# InkTime.net
KiCad netlist of a schematic drawn in EAGLE
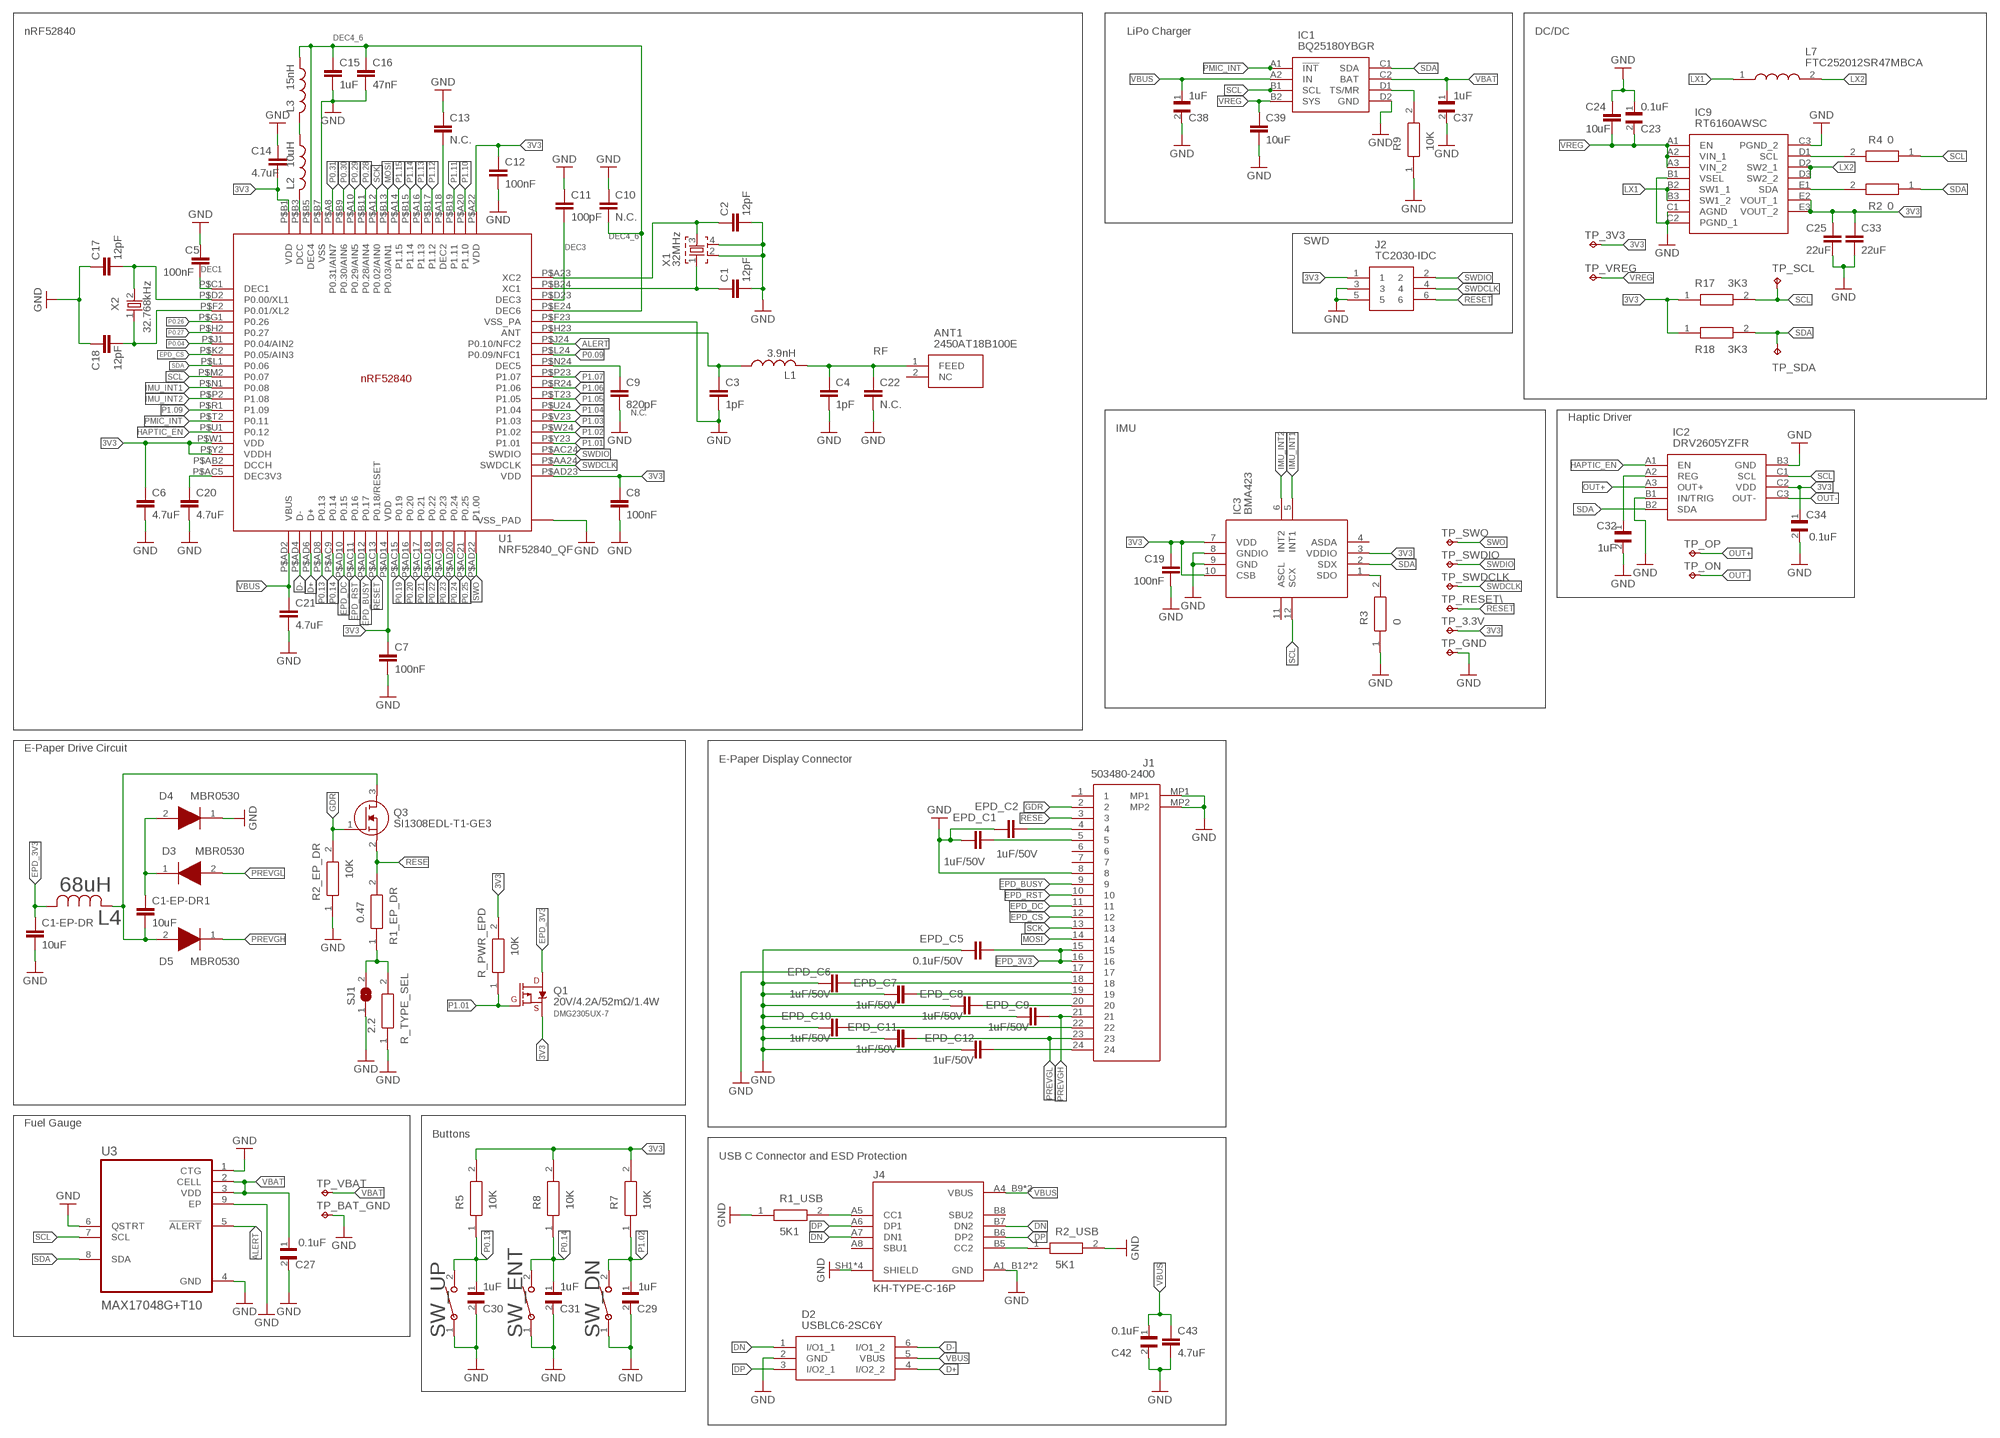
[diagram p0: schematic, sheet 1]

(export (version "E")
  (design (tool "Eeschema 10.0.6"))
  (components
    (comp (ref "ANT1")
      (value "2450AT18B100E")
      (footprint "eagle-import:2450AT18B100E_ANTC3216X140N")
      (fields (field (name "MOUSER_PART_NUMBER") "609-2450AT18B100E"))
      (libsource (lib "eagle-import") (part "2450AT18B100E_2450AT18B100E"))
    )
    (comp (ref "C1")
      (value "12pF")
      (footprint "eagle-import:NORDIC_NRF_3_RESC0201_L")
      (libsource (lib "eagle-import") (part "InkTime_v5_vf.MLmYuSJKQ5Wbrkh9WamEiQ_NORDIC_NRF_3_CAPACITOR_0201_L"))
    )
    (comp (ref "C1-EP-DR")
      (value "10uF")
      (footprint "eagle-import:NORDIC_NRF_3_RESC0402_L")
      (libsource (lib "eagle-import") (part "InkTime_v5_vf.MLmYuSJKQ5Wbrkh9WamEiQ_NORDIC_NRF_3_CAPACITOR_0402_L"))
    )
    (comp (ref "C1-EP-DR1")
      (value "10uF")
      (footprint "eagle-import:NORDIC_NRF_3_RESC0402_L")
      (libsource (lib "eagle-import") (part "InkTime_v5_vf.MLmYuSJKQ5Wbrkh9WamEiQ_NORDIC_NRF_3_CAPACITOR_0402_L"))
    )
    (comp (ref "C2")
      (value "12pF")
      (footprint "eagle-import:NORDIC_NRF_3_RESC0201_L")
      (libsource (lib "eagle-import") (part "InkTime_v5_vf.MLmYuSJKQ5Wbrkh9WamEiQ_NORDIC_NRF_3_CAPACITOR_0201_L"))
    )
    (comp (ref "C3")
      (value "1pF")
      (footprint "eagle-import:NORDIC_NRF_3_RESC0201_L")
      (libsource (lib "eagle-import") (part "InkTime_v5_vf.MLmYuSJKQ5Wbrkh9WamEiQ_NORDIC_NRF_3_CAPACITOR_0201_L"))
    )
    (comp (ref "C4")
      (value "1pF")
      (footprint "eagle-import:NORDIC_NRF_3_RESC0201_L")
      (libsource (lib "eagle-import") (part "InkTime_v5_vf.MLmYuSJKQ5Wbrkh9WamEiQ_NORDIC_NRF_3_CAPACITOR_0201_L"))
    )
    (comp (ref "C5")
      (value "100nF")
      (footprint "eagle-import:NORDIC_NRF_3_RESC0201_L")
      (libsource (lib "eagle-import") (part "InkTime_v5_vf.MLmYuSJKQ5Wbrkh9WamEiQ_NORDIC_NRF_3_CAPACITOR_0201_L"))
    )
    (comp (ref "C6")
      (value "4.7uF")
      (footprint "eagle-import:NORDIC_NRF_3_RESC0402_L")
      (libsource (lib "eagle-import") (part "InkTime_v5_vf.MLmYuSJKQ5Wbrkh9WamEiQ_NORDIC_NRF_3_CAPACITOR_0402_L"))
    )
    (comp (ref "C7")
      (value "100nF")
      (footprint "eagle-import:NORDIC_NRF_3_RESC0201_L")
      (libsource (lib "eagle-import") (part "InkTime_v5_vf.MLmYuSJKQ5Wbrkh9WamEiQ_NORDIC_NRF_3_CAPACITOR_0201_L"))
    )
    (comp (ref "C8")
      (value "100nF")
      (footprint "eagle-import:NORDIC_NRF_3_RESC0201_L")
      (libsource (lib "eagle-import") (part "InkTime_v5_vf.MLmYuSJKQ5Wbrkh9WamEiQ_NORDIC_NRF_3_CAPACITOR_0201_L"))
    )
    (comp (ref "C9")
      (value "820pF")
      (footprint "eagle-import:NORDIC_NRF_3_RESC0201_L")
      (libsource (lib "eagle-import") (part "InkTime_v5_vf.MLmYuSJKQ5Wbrkh9WamEiQ_NORDIC_NRF_3_CAPACITOR_0201_L"))
    )
    (comp (ref "C10")
      (value "N.C.")
      (footprint "eagle-import:NORDIC_NRF_3_RESC0201_L")
      (libsource (lib "eagle-import") (part "InkTime_v5_vf.MLmYuSJKQ5Wbrkh9WamEiQ_NORDIC_NRF_3_CAPACITOR_0201_L"))
    )
    (comp (ref "C11")
      (value "100pF")
      (footprint "eagle-import:NORDIC_NRF_3_RESC0201_L")
      (libsource (lib "eagle-import") (part "InkTime_v5_vf.MLmYuSJKQ5Wbrkh9WamEiQ_NORDIC_NRF_3_CAPACITOR_0201_L"))
    )
    (comp (ref "C12")
      (value "100nF")
      (footprint "eagle-import:NORDIC_NRF_3_RESC0201_L")
      (libsource (lib "eagle-import") (part "InkTime_v5_vf.MLmYuSJKQ5Wbrkh9WamEiQ_NORDIC_NRF_3_CAPACITOR_0201_L"))
    )
    (comp (ref "C13")
      (value "N.C.")
      (footprint "eagle-import:NORDIC_NRF_3_RESC0201_L")
      (libsource (lib "eagle-import") (part "InkTime_v5_vf.MLmYuSJKQ5Wbrkh9WamEiQ_NORDIC_NRF_3_CAPACITOR_0201_L"))
    )
    (comp (ref "C14")
      (value "4.7uF")
      (footprint "eagle-import:NORDIC_NRF_3_RESC0402_L")
      (libsource (lib "eagle-import") (part "InkTime_v5_vf.MLmYuSJKQ5Wbrkh9WamEiQ_NORDIC_NRF_3_CAPACITOR_0402_L"))
    )
    (comp (ref "C15")
      (value "1uF")
      (footprint "eagle-import:NORDIC_NRF_3_RESC0402_L")
      (libsource (lib "eagle-import") (part "InkTime_v5_vf.MLmYuSJKQ5Wbrkh9WamEiQ_NORDIC_NRF_3_CAPACITOR_0402_L"))
    )
    (comp (ref "C16")
      (value "47nF")
      (footprint "eagle-import:NORDIC_NRF_3_RESC0201_L")
      (libsource (lib "eagle-import") (part "InkTime_v5_vf.MLmYuSJKQ5Wbrkh9WamEiQ_NORDIC_NRF_3_CAPACITOR_0201_L"))
    )
    (comp (ref "C17")
      (value "12pF")
      (footprint "eagle-import:NORDIC_NRF_3_RESC0201_L")
      (libsource (lib "eagle-import") (part "InkTime_v5_vf.MLmYuSJKQ5Wbrkh9WamEiQ_NORDIC_NRF_3_CAPACITOR_0201_L"))
    )
    (comp (ref "C18")
      (value "12pF")
      (footprint "eagle-import:NORDIC_NRF_3_RESC0201_L")
      (libsource (lib "eagle-import") (part "InkTime_v5_vf.MLmYuSJKQ5Wbrkh9WamEiQ_NORDIC_NRF_3_CAPACITOR_0201_L"))
    )
    (comp (ref "C19")
      (value "100nF")
      (footprint "eagle-import:NORDIC_NRF_3_RESC0201_L")
      (libsource (lib "eagle-import") (part "InkTime_v5_vf.MLmYuSJKQ5Wbrkh9WamEiQ_NORDIC_NRF_3_CAPACITOR_0201_L"))
    )
    (comp (ref "C20")
      (value "4.7uF")
      (footprint "eagle-import:NORDIC_NRF_3_RESC0402_L")
      (libsource (lib "eagle-import") (part "InkTime_v5_vf.MLmYuSJKQ5Wbrkh9WamEiQ_NORDIC_NRF_3_CAPACITOR_0402_L"))
    )
    (comp (ref "C21")
      (value "4.7uF")
      (footprint "eagle-import:NORDIC_NRF_3_RESC0402_L")
      (libsource (lib "eagle-import") (part "InkTime_v5_vf.MLmYuSJKQ5Wbrkh9WamEiQ_NORDIC_NRF_3_CAPACITOR_0402_L"))
    )
    (comp (ref "C22")
      (value "N.C.")
      (footprint "eagle-import:NORDIC_NRF_3_RESC0201_L")
      (libsource (lib "eagle-import") (part "InkTime_v5_vf.MLmYuSJKQ5Wbrkh9WamEiQ_NORDIC_NRF_3_CAPACITOR_0201_L"))
    )
    (comp (ref "C23")
      (value "0.1uF")
      (footprint "eagle-import:GRM011R60J152KE01L_2_CAPC0201X13N")
      (fields (field (name "MF") "Murata") (field (name "MP") "GRM011R60J152KE01L"))
      (libsource (lib "eagle-import") (part "GRM011R60J152KE01L_2_GRM011R60J152KE01L"))
    )
    (comp (ref "C24")
      (value "10uF")
      (footprint "eagle-import:NORDIC_NRF_3_RESC0402_L")
      (libsource (lib "eagle-import") (part "InkTime_v5_vf.MLmYuSJKQ5Wbrkh9WamEiQ_NORDIC_NRF_3_CAPACITOR_0402_L"))
    )
    (comp (ref "C25")
      (value "22uF")
      (footprint "eagle-import:NORDIC_NRF_3_RESC0402_L")
      (libsource (lib "eagle-import") (part "InkTime_v5_vf.MLmYuSJKQ5Wbrkh9WamEiQ_NORDIC_NRF_3_CAPACITOR_0402_L"))
    )
    (comp (ref "C27")
      (value "0.1uF")
      (footprint "eagle-import:GRM011R60J152KE01L_2_CAPC0201X13N")
      (fields (field (name "MF") "Murata") (field (name "MP") "GRM011R60J152KE01L"))
      (libsource (lib "eagle-import") (part "GRM011R60J152KE01L_2_GRM011R60J152KE01L"))
    )
    (comp (ref "C29")
      (value "1uF")
      (footprint "eagle-import:GRM011R60J152KE01L_2_CAPC0201X13N")
      (fields (field (name "MF") "Murata") (field (name "MP") "GRM011R60J152KE01L"))
      (libsource (lib "eagle-import") (part "GRM011R60J152KE01L_2_GRM011R60J152KE01L"))
    )
    (comp (ref "C30")
      (value "1uF")
      (footprint "eagle-import:GRM011R60J152KE01L_2_CAPC0201X13N")
      (fields (field (name "MF") "Murata") (field (name "MP") "GRM011R60J152KE01L"))
      (libsource (lib "eagle-import") (part "GRM011R60J152KE01L_2_GRM011R60J152KE01L"))
    )
    (comp (ref "C31")
      (value "1uF")
      (footprint "eagle-import:GRM011R60J152KE01L_2_CAPC0201X13N")
      (fields (field (name "MF") "Murata") (field (name "MP") "GRM011R60J152KE01L"))
      (libsource (lib "eagle-import") (part "GRM011R60J152KE01L_2_GRM011R60J152KE01L"))
    )
    (comp (ref "C32")
      (value "1uF")
      (footprint "eagle-import:GRM011R60J152KE01L_2_CAPC0201X13N")
      (fields (field (name "MF") "Murata") (field (name "MP") "GRM011R60J152KE01L"))
      (libsource (lib "eagle-import") (part "GRM011R60J152KE01L_2_GRM011R60J152KE01L"))
    )
    (comp (ref "C33")
      (value "22uF")
      (footprint "eagle-import:NORDIC_NRF_3_RESC0402_L")
      (libsource (lib "eagle-import") (part "InkTime_v5_vf.MLmYuSJKQ5Wbrkh9WamEiQ_NORDIC_NRF_3_CAPACITOR_0402_L"))
    )
    (comp (ref "C34")
      (value "0.1uF")
      (footprint "eagle-import:GRM011R60J152KE01L_2_CAPC0201X13N")
      (fields (field (name "MF") "Murata") (field (name "MP") "GRM011R60J152KE01L"))
      (libsource (lib "eagle-import") (part "GRM011R60J152KE01L_2_GRM011R60J152KE01L"))
    )
    (comp (ref "C37")
      (value "1uF")
      (footprint "eagle-import:GRM011R60J152KE01L_2_CAPC0201X13N")
      (fields (field (name "MF") "Murata") (field (name "MP") "GRM011R60J152KE01L"))
      (libsource (lib "eagle-import") (part "GRM011R60J152KE01L_2_GRM011R60J152KE01L"))
    )
    (comp (ref "C38")
      (value "1uF")
      (footprint "eagle-import:GRM011R60J152KE01L_2_CAPC0201X13N")
      (fields (field (name "MF") "Murata") (field (name "MP") "GRM011R60J152KE01L"))
      (libsource (lib "eagle-import") (part "GRM011R60J152KE01L_2_GRM011R60J152KE01L"))
    )
    (comp (ref "C39")
      (value "10uF")
      (footprint "eagle-import:NORDIC_NRF_3_RESC0402_L")
      (libsource (lib "eagle-import") (part "InkTime_v5_vf.MLmYuSJKQ5Wbrkh9WamEiQ_NORDIC_NRF_3_CAPACITOR_0402_L"))
    )
    (comp (ref "C42")
      (value "0.1uF")
      (footprint "eagle-import:GRM011R60J152KE01L_2_CAPC0201X13N")
      (fields (field (name "MF") "Murata") (field (name "MP") "GRM011R60J152KE01L"))
      (libsource (lib "eagle-import") (part "GRM011R60J152KE01L_2_GRM011R60J152KE01L"))
    )
    (comp (ref "C43")
      (value "4.7uF")
      (footprint "eagle-import:NORDIC_NRF_3_RESC0402_L")
      (libsource (lib "eagle-import") (part "InkTime_v5_vf.MLmYuSJKQ5Wbrkh9WamEiQ_NORDIC_NRF_3_CAPACITOR_0402_L"))
    )
    (comp (ref "D2")
      (value "USBLC6-2SC6Y")
      (footprint "eagle-import:ESP32_C6_LIBRARY_3_SOT95P280X145-6N")
      (fields (field (name "MF") "STMicroelectronics"))
      (libsource (lib "eagle-import") (part "ESP32_C6_LIBRARY_3_USBLC6-2SC6Y"))
    )
    (comp (ref "D3")
      (value "MBR0530")
      (footprint "eagle-import:ESP32_C6_LIBRARY_5_SOD3716X135N")
      (fields (field (name "MF") "ON Semiconductor"))
      (libsource (lib "eagle-import") (part "ESP32_C6_LIBRARY_5_MBR0530"))
    )
    (comp (ref "D4")
      (value "MBR0530")
      (footprint "eagle-import:ESP32_C6_LIBRARY_5_SOD3716X135N")
      (fields (field (name "MF") "ON Semiconductor"))
      (libsource (lib "eagle-import") (part "ESP32_C6_LIBRARY_5_MBR0530"))
    )
    (comp (ref "D5")
      (value "MBR0530")
      (footprint "eagle-import:ESP32_C6_LIBRARY_5_SOD3716X135N")
      (fields (field (name "MF") "ON Semiconductor"))
      (libsource (lib "eagle-import") (part "ESP32_C6_LIBRARY_5_MBR0530"))
    )
    (comp (ref "EPD_C1")
      (value "1uF/50V")
      (footprint "eagle-import:NORDIC_NRF_3_RESC0402_L")
      (libsource (lib "eagle-import") (part "InkTime_v5_vf.MLmYuSJKQ5Wbrkh9WamEiQ_NORDIC_NRF_3_CAPACITOR_0402_L"))
    )
    (comp (ref "EPD_C2")
      (value "1uF/50V")
      (footprint "eagle-import:NORDIC_NRF_3_RESC0402_L")
      (libsource (lib "eagle-import") (part "InkTime_v5_vf.MLmYuSJKQ5Wbrkh9WamEiQ_NORDIC_NRF_3_CAPACITOR_0402_L"))
    )
    (comp (ref "EPD_C5")
      (value "0.1uF/50V")
      (footprint "eagle-import:NORDIC_NRF_3_RESC0201_L")
      (libsource (lib "eagle-import") (part "NORDIC_NRF_3_CAPACITOR_0201_L"))
    )
    (comp (ref "EPD_C6")
      (value "1uF/50V")
      (footprint "eagle-import:NORDIC_NRF_3_RESC0402_L")
      (libsource (lib "eagle-import") (part "InkTime_v5_vf.MLmYuSJKQ5Wbrkh9WamEiQ_NORDIC_NRF_3_CAPACITOR_0402_L"))
    )
    (comp (ref "EPD_C7")
      (value "1uF/50V")
      (footprint "eagle-import:NORDIC_NRF_3_RESC0402_L")
      (libsource (lib "eagle-import") (part "InkTime_v5_vf.MLmYuSJKQ5Wbrkh9WamEiQ_NORDIC_NRF_3_CAPACITOR_0402_L"))
    )
    (comp (ref "EPD_C8")
      (value "1uF/50V")
      (footprint "eagle-import:NORDIC_NRF_3_RESC0402_L")
      (libsource (lib "eagle-import") (part "InkTime_v5_vf.MLmYuSJKQ5Wbrkh9WamEiQ_NORDIC_NRF_3_CAPACITOR_0402_L"))
    )
    (comp (ref "EPD_C9")
      (value "1uF/50V")
      (footprint "eagle-import:NORDIC_NRF_3_RESC0402_L")
      (libsource (lib "eagle-import") (part "InkTime_v5_vf.MLmYuSJKQ5Wbrkh9WamEiQ_NORDIC_NRF_3_CAPACITOR_0402_L"))
    )
    (comp (ref "EPD_C10")
      (value "1uF/50V")
      (footprint "eagle-import:NORDIC_NRF_3_RESC0402_L")
      (libsource (lib "eagle-import") (part "InkTime_v5_vf.MLmYuSJKQ5Wbrkh9WamEiQ_NORDIC_NRF_3_CAPACITOR_0402_L"))
    )
    (comp (ref "EPD_C11")
      (value "1uF/50V")
      (footprint "eagle-import:NORDIC_NRF_3_RESC0402_L")
      (libsource (lib "eagle-import") (part "InkTime_v5_vf.MLmYuSJKQ5Wbrkh9WamEiQ_NORDIC_NRF_3_CAPACITOR_0402_L"))
    )
    (comp (ref "EPD_C12")
      (value "1uF/50V")
      (footprint "eagle-import:NORDIC_NRF_3_RESC0402_L")
      (libsource (lib "eagle-import") (part "InkTime_v5_vf.MLmYuSJKQ5Wbrkh9WamEiQ_NORDIC_NRF_3_CAPACITOR_0402_L"))
    )
    (comp (ref "IC1")
      (value "BQ25180YBGR")
      (footprint "eagle-import:BQ25180YBGR_BGA8C40P2X4_100X155X50")
      (fields (field (name "MOUSER_PART_NUMBER") "595-BQ25180YBGR"))
      (libsource (lib "eagle-import") (part "BQ25180YBGR_BQ25180YBGR"))
    )
    (comp (ref "IC2")
      (value "DRV2605YZFR")
      (footprint "eagle-import:DRV2605YZFR_BGA9C50P3X3_144X144X62")
      (libsource (lib "eagle-import") (part "DRV2605YZFR_DRV2605YZFR"))
    )
    (comp (ref "IC3")
      (value "BMA423")
      (footprint "eagle-import:BMA423_BMA423")
      (fields (field (name "MOUSER_PART_NUMBER") "262-BMA423"))
      (libsource (lib "eagle-import") (part "BMA423_BMA423"))
    )
    (comp (ref "IC9")
      (value "RT6160AWSC")
      (footprint "eagle-import:RT6160AWSC_BGA15C40P3X5_140X230X60")
      (fields (field (name "MOUSER_PART_NUMBER") "835-RT6160AWSC"))
      (libsource (lib "eagle-import") (part "RT6160AWSC_RT6160AWSC"))
    )
    (comp (ref "J1")
      (value "503480-2400")
      (footprint "eagle-import:503480-2400_5034802400")
      (fields (field (name "MOUSER_PART_NUMBER") "538-503480-2400"))
      (libsource (lib "eagle-import") (part "503480-2400_503480-2400"))
    )
    (comp (ref "J2")
      (value "TC2030-IDC")
      (footprint "eagle-import:TC2030-IDC_TC2030IDC")
      (libsource (lib "eagle-import") (part "TC2030-IDC_TC2030-IDC"))
    )
    (comp (ref "J4")
      (value "KH-TYPE-C-16P")
      (footprint "eagle-import:KH-TYPE-C-16P_KINGHELM_KH-TYPE-C-16P")
      (fields (field (name "MF") "kinghelm"))
      (libsource (lib "eagle-import") (part "KH-TYPE-C-16P_KH-TYPE-C-16P"))
    )
    (comp (ref "L1")
      (value "3.9nH")
      (footprint "eagle-import:NORDIC_NRF_2_RESC0201_L")
      (libsource (lib "eagle-import") (part "NORDIC_NRF_2_INDUCTOR_0201_L"))
    )
    (comp (ref "L2")
      (value "10uH")
      (footprint "eagle-import:NORDIC_NRF_2_RESC0402_L")
      (libsource (lib "eagle-import") (part "NORDIC_NRF_2_INDUCTOR_0402_L"))
    )
    (comp (ref "L3")
      (value "15nH")
      (footprint "eagle-import:NORDIC_NRF_2_RESC0201_L")
      (libsource (lib "eagle-import") (part "NORDIC_NRF_2_INDUCTOR_0201_L"))
    )
    (comp (ref "L4")
      (value "68uH")
      (footprint "eagle-import:ESP32_C6_LIBRARY_2_IND_4828-WE-TPC_WRE")
      (fields
        (field (name "MANUFACTURER_PART_NUMBER") "744043680")
        (field (name "COPYRIGHT") "Copyright (C) 2024 Ultra Librarian. All rights reserved.")
      )
      (libsource (lib "eagle-import") (part "ESP32_C6_LIBRARY_2_744043680IND_4828-WE-TPC_WRE"))
    )
    (comp (ref "L7")
      (value "FTC252012SR47MBCA")
      (footprint "eagle-import:MLP2016SR47MT0S1_INDC2016X100N")
      (libsource (lib "eagle-import") (part "MLP2016SR47MT0S1_FTC252012SR47MBCA"))
    )
    (comp (ref "Q1")
      (value "20V/4.2A/52mΩ/1.4W")
      (footprint "eagle-import:ESP32_C6_LIBRARY_4_ESP32_C6_LIBRARY_4_ESP32_C6_LIBRARY_4_ESP32_C6_LIBRARY_4_ESP32_WROVER_SPARKFUN-DISCRETESEMI_SOT23-3")
      (libsource (lib "eagle-import") (part "ESP32_C6_LIBRARY_4_ESP32_WROVER_SPARKFUN-DISCRETESEMI_MOSFET_PCH-DMG2305UX-7"))
    )
    (comp (ref "Q3")
      (value "SI1308EDL-T1-GE3")
      (footprint "eagle-import:ESP32_C6_LIBRARY_6_SOT65P210X110-3N")
      (fields (field (name "MF") "Vishay Siliconix"))
      (libsource (lib "eagle-import") (part "ESP32_C6_LIBRARY_6_SI1308EDL-T1-GE3"))
    )
    (comp (ref "R1_EP_DR")
      (value "0.47")
      (footprint "eagle-import:CPF0201D7K68C1_0201")
      (libsource (lib "eagle-import") (part "CPF0201D7K68C1_CPF0201D7K68C1"))
    )
    (comp (ref "R1_USB")
      (value "5K1")
      (footprint "eagle-import:ERA-1AEB3401C_0201")
      (libsource (lib "eagle-import") (part "ERA-1AEB3401C_CPF0201D7K68C1"))
    )
    (comp (ref "R2")
      (value "0")
      (footprint "eagle-import:CPF0201D7K68C1_0201")
      (libsource (lib "eagle-import") (part "CPF0201D7K68C1_CPF0201D7K68C1"))
    )
    (comp (ref "R2_EP_DR")
      (value "10K")
      (footprint "eagle-import:CPF0201D7K68C1_0201")
      (libsource (lib "eagle-import") (part "CPF0201D7K68C1_CPF0201D7K68C1"))
    )
    (comp (ref "R2_USB")
      (value "5K1")
      (footprint "eagle-import:ERA-1AEB3401C_0201")
      (libsource (lib "eagle-import") (part "ERA-1AEB3401C_CPF0201D7K68C1"))
    )
    (comp (ref "R3")
      (value "0")
      (footprint "eagle-import:CPF0201D7K68C1_0201")
      (libsource (lib "eagle-import") (part "CPF0201D7K68C1_CPF0201D7K68C1"))
    )
    (comp (ref "R4")
      (value "0")
      (footprint "eagle-import:CPF0201D7K68C1_0201")
      (libsource (lib "eagle-import") (part "CPF0201D7K68C1_CPF0201D7K68C1"))
    )
    (comp (ref "R5")
      (value "10K")
      (footprint "eagle-import:CPF0201D7K68C1_0201")
      (libsource (lib "eagle-import") (part "CPF0201D7K68C1_CPF0201D7K68C1"))
    )
    (comp (ref "R7")
      (value "10K")
      (footprint "eagle-import:CPF0201D7K68C1_0201")
      (libsource (lib "eagle-import") (part "CPF0201D7K68C1_CPF0201D7K68C1"))
    )
    (comp (ref "R8")
      (value "10K")
      (footprint "eagle-import:CPF0201D7K68C1_0201")
      (libsource (lib "eagle-import") (part "CPF0201D7K68C1_CPF0201D7K68C1"))
    )
    (comp (ref "R9")
      (value "10K")
      (footprint "eagle-import:CPF0201D7K68C1_0201")
      (libsource (lib "eagle-import") (part "CPF0201D7K68C1_CPF0201D7K68C1"))
    )
    (comp (ref "R17")
      (value "3K3")
      (footprint "eagle-import:CPF0201D7K68C1_0201")
      (libsource (lib "eagle-import") (part "CPF0201D7K68C1_CPF0201D7K68C1"))
    )
    (comp (ref "R18")
      (value "3K3")
      (footprint "eagle-import:CPF0201D7K68C1_0201")
      (libsource (lib "eagle-import") (part "CPF0201D7K68C1_CPF0201D7K68C1"))
    )
    (comp (ref "R_PWR_EPD")
      (value "10K")
      (footprint "eagle-import:CPF0201D7K68C1_0201")
      (libsource (lib "eagle-import") (part "CPF0201D7K68C1_CPF0201D7K68C1"))
    )
    (comp (ref "R_TYPE_SEL")
      (value "2.2")
      (footprint "eagle-import:CPF0201D7K68C1_0201")
      (libsource (lib "eagle-import") (part "CPF0201D7K68C1_CPF0201D7K68C1"))
    )
    (comp (ref "SJ1")
      (value "JUMPER_SJ")
      (footprint "eagle-import:ESP32_C6_LIBRARY_7_JUMPER_SJ")
      (libsource (lib "eagle-import") (part "ESP32_C6_LIBRARY_7_JUMPER_SJ"))
    )
    (comp (ref "SW_DN")
      (value "2025-10-22_07-23-44_LIBRARY_EVP-AKE31ASW_EVP-AKE31A_PAN")
      (footprint "eagle-import:2025-10-22_07-23-44_LIBRARY_SW_EVP-AKE31A_PAN")
      (fields
        (field (name "MANUFACTURER_PART_NUMBER") "EVP-AKE31A")
        (field (name "COPYRIGHT") "Copyright (C) 2025 Ultra Librarian. All rights reserved.")
      )
      (libsource (lib "eagle-import") (part "2025-10-22_07-23-44_LIBRARY_EVP-AKE31ASW_EVP-AKE31A_PAN"))
    )
    (comp (ref "SW_ENT")
      (value "2025-10-22_07-23-44_LIBRARY_EVP-AKE31ASW_EVP-AKE31A_PAN")
      (footprint "eagle-import:2025-10-22_07-23-44_LIBRARY_SW_EVP-AKE31A_PAN")
      (fields
        (field (name "MANUFACTURER_PART_NUMBER") "EVP-AKE31A")
        (field (name "COPYRIGHT") "Copyright (C) 2025 Ultra Librarian. All rights reserved.")
      )
      (libsource (lib "eagle-import") (part "2025-10-22_07-23-44_LIBRARY_EVP-AKE31ASW_EVP-AKE31A_PAN"))
    )
    (comp (ref "SW_UP")
      (value "2025-10-22_07-23-44_LIBRARY_EVP-AKE31ASW_EVP-AKE31A_PAN")
      (footprint "eagle-import:2025-10-22_07-23-44_LIBRARY_SW_EVP-AKE31A_PAN")
      (fields
        (field (name "MANUFACTURER_PART_NUMBER") "EVP-AKE31A")
        (field (name "COPYRIGHT") "Copyright (C) 2025 Ultra Librarian. All rights reserved.")
      )
      (libsource (lib "eagle-import") (part "2025-10-22_07-23-44_LIBRARY_EVP-AKE31ASW_EVP-AKE31A_PAN"))
    )
    (comp (ref "TP_3.3V")
      (value "HECTOR_WATCH_1_TPTP20R")
      (footprint "eagle-import:HECTOR_WATCH_1_TP20R")
      (libsource (lib "eagle-import") (part "HECTOR_WATCH_1_TPTP20R"))
    )
    (comp (ref "TP_3V3")
      (value "HECTOR_WATCH_1_TPTP20R")
      (footprint "eagle-import:HECTOR_WATCH_1_TP20R")
      (libsource (lib "eagle-import") (part "HECTOR_WATCH_1_TPTP20R"))
    )
    (comp (ref "TP_BAT_GND")
      (value "HECTOR_WATCH_1_TPTP20R")
      (footprint "eagle-import:HECTOR_WATCH_1_TP20R")
      (libsource (lib "eagle-import") (part "HECTOR_WATCH_1_TPTP20R"))
    )
    (comp (ref "TP_GND")
      (value "HECTOR_WATCH_1_TPTP20R")
      (footprint "eagle-import:HECTOR_WATCH_1_TP20R")
      (libsource (lib "eagle-import") (part "HECTOR_WATCH_1_TPTP20R"))
    )
    (comp (ref "TP_ON")
      (value "HECTOR_WATCH_1_TPTP20R")
      (footprint "eagle-import:HECTOR_WATCH_1_TP20R")
      (libsource (lib "eagle-import") (part "HECTOR_WATCH_1_TPTP20R"))
    )
    (comp (ref "TP_OP")
      (value "HECTOR_WATCH_1_TPTP20R")
      (footprint "eagle-import:HECTOR_WATCH_1_TP20R")
      (libsource (lib "eagle-import") (part "HECTOR_WATCH_1_TPTP20R"))
    )
    (comp (ref "TP_RESET\\")
      (value "HECTOR_WATCH_1_TPTP20R")
      (footprint "eagle-import:HECTOR_WATCH_1_TP20R")
      (libsource (lib "eagle-import") (part "HECTOR_WATCH_1_TPTP20R"))
    )
    (comp (ref "TP_SCL")
      (value "HECTOR_WATCH_1_TPTP20R")
      (footprint "eagle-import:HECTOR_WATCH_1_TP20R")
      (libsource (lib "eagle-import") (part "HECTOR_WATCH_1_TPTP20R"))
    )
    (comp (ref "TP_SDA")
      (value "HECTOR_WATCH_1_TPTP20R")
      (footprint "eagle-import:HECTOR_WATCH_1_TP20R")
      (libsource (lib "eagle-import") (part "HECTOR_WATCH_1_TPTP20R"))
    )
    (comp (ref "TP_SWDCLK")
      (value "HECTOR_WATCH_1_TPTP20R")
      (footprint "eagle-import:HECTOR_WATCH_1_TP20R")
      (libsource (lib "eagle-import") (part "HECTOR_WATCH_1_TPTP20R"))
    )
    (comp (ref "TP_SWDIO")
      (value "HECTOR_WATCH_1_TPTP20R")
      (footprint "eagle-import:HECTOR_WATCH_1_TP20R")
      (libsource (lib "eagle-import") (part "HECTOR_WATCH_1_TPTP20R"))
    )
    (comp (ref "TP_SWO")
      (value "HECTOR_WATCH_1_TPTP20R")
      (footprint "eagle-import:HECTOR_WATCH_1_TP20R")
      (libsource (lib "eagle-import") (part "HECTOR_WATCH_1_TPTP20R"))
    )
    (comp (ref "TP_VBAT")
      (value "HECTOR_WATCH_1_TPTP20R")
      (footprint "eagle-import:HECTOR_WATCH_1_TP20R")
      (libsource (lib "eagle-import") (part "HECTOR_WATCH_1_TPTP20R"))
    )
    (comp (ref "TP_VREG")
      (value "HECTOR_WATCH_1_TPTP20R")
      (footprint "eagle-import:HECTOR_WATCH_1_TP20R")
      (libsource (lib "eagle-import") (part "HECTOR_WATCH_1_TPTP20R"))
    )
    (comp (ref "U1")
      (value "NRF52840_QF")
      (footprint "eagle-import:NORDIC_NRF_4_AQFN50P700X700X85_HS-74N")
      (libsource (lib "eagle-import") (part "NORDIC_NRF_4_NRF52840_QF"))
    )
    (comp (ref "U3")
      (value "MAX17048G+T10")
      (footprint "eagle-import:ESP32_C6_LIBRARY_SON50P200X200X80-9N")
      (fields (field (name "MF") "Analog Devices"))
      (libsource (lib "eagle-import") (part "ESP32_C6_LIBRARY_MAX17048G+T10"))
    )
    (comp (ref "X1")
      (value "32MHz")
      (footprint "eagle-import:NORDIC_NRF_BT-XTAL_2016_N")
      (libsource (lib "eagle-import") (part "NORDIC_NRF_XTAL_32MHZ"))
    )
    (comp (ref "X2")
      (value "32.768kHz")
      (footprint "eagle-import:NORDIC_NRF_1_XTAL_3215_N")
      (libsource (lib "eagle-import") (part "NORDIC_NRF_1_XTAL_32KHZ"))
    )
  )
  (nets
    (net (code "1") (name "3V3") (class "Default")
      (node (ref "C12") (pin "1") (pinfunction "1_1") (pintype "passive"))
      (node (ref "C14") (pin "2") (pinfunction "2_2") (pintype "passive"))
      (node (ref "C19") (pin "1") (pinfunction "1_1") (pintype "passive"))
      (node (ref "C25") (pin "1") (pinfunction "1_1") (pintype "passive"))
      (node (ref "C33") (pin "1") (pinfunction "1_1") (pintype "passive"))
      (node (ref "C34") (pin "1") (pinfunction "1_1") (pintype "passive"))
      (node (ref "C6") (pin "1") (pinfunction "1_1") (pintype "passive"))
      (node (ref "C7") (pin "1") (pinfunction "1_1") (pintype "passive"))
      (node (ref "C8") (pin "1") (pinfunction "1_1") (pintype "passive"))
      (node (ref "IC2") (pin "C2") (pinfunction "VDD_C2") (pintype "bidirectional"))
      (node (ref "IC3") (pin "10") (pinfunction "CSB_10") (pintype "bidirectional"))
      (node (ref "IC3") (pin "3") (pinfunction "VDDIO_3") (pintype "bidirectional"))
      (node (ref "IC3") (pin "7") (pinfunction "VDD_7") (pintype "bidirectional"))
      (node (ref "IC9") (pin "E2") (pinfunction "VOUT_1_E2") (pintype "bidirectional"))
      (node (ref "IC9") (pin "E3") (pinfunction "VOUT_2_E3") (pintype "bidirectional"))
      (node (ref "J2") (pin "1") (pinfunction "1_1") (pintype "bidirectional"))
      (node (ref "Q1") (pin "2") (pinfunction "S_2") (pintype "bidirectional"))
      (node (ref "R17") (pin "1") (pinfunction "1_1") (pintype "bidirectional"))
      (node (ref "R18") (pin "1") (pinfunction "1_1") (pintype "bidirectional"))
      (node (ref "R5") (pin "2") (pinfunction "2_2") (pintype "bidirectional"))
      (node (ref "R7") (pin "2") (pinfunction "2_2") (pintype "bidirectional"))
      (node (ref "R8") (pin "2") (pinfunction "2_2") (pintype "bidirectional"))
      (node (ref "R_PWR_EPD") (pin "2") (pinfunction "2_2") (pintype "bidirectional"))
      (node (ref "TP_3.3V") (pin "TP") (pinfunction "TP_TP") (pintype "input"))
      (node (ref "TP_3V3") (pin "TP") (pinfunction "TP_TP") (pintype "input"))
      (node (ref "U1") (pin "P$A22") (pinfunction "VDD_P$A22") (pintype "power_in"))
      (node (ref "U1") (pin "P$AD14") (pinfunction "VDD_P$AD14") (pintype "power_in"))
      (node (ref "U1") (pin "P$AD23") (pinfunction "VDD_P$AD23") (pintype "power_in"))
      (node (ref "U1") (pin "P$B1") (pinfunction "VDD_P$B1") (pintype "power_in"))
      (node (ref "U1") (pin "P$W1") (pinfunction "VDD_P$W1") (pintype "power_in"))
      (node (ref "U1") (pin "P$Y2") (pinfunction "VDDH_P$Y2") (pintype "power_in"))
    )
    (net (code "2") (name "ALERT") (class "Default")
      (node (ref "U1") (pin "P$J24") (pinfunction "P0.10/NFC2_P$J24") (pintype "bidirectional"))
      (node (ref "U3") (pin "5") (pinfunction "~{ALERT}_5") (pintype "output"))
    )
    (net (code "3") (name "D+") (class "Default")
      (node (ref "D2") (pin "4") (pinfunction "I/O2_2_4") (pintype "bidirectional"))
      (node (ref "U1") (pin "P$AD6") (pinfunction "D+_P$AD6") (pintype "bidirectional"))
    )
    (net (code "4") (name "D-") (class "Default")
      (node (ref "D2") (pin "6") (pinfunction "I/O1_2_6") (pintype "bidirectional"))
      (node (ref "U1") (pin "P$AD4") (pinfunction "D-_P$AD4") (pintype "bidirectional"))
    )
    (net (code "5") (name "DN") (class "Default")
      (node (ref "D2") (pin "1") (pinfunction "I/O1_1_1") (pintype "bidirectional"))
      (node (ref "J4") (pin "A7") (pinfunction "DN1_A7") (pintype "bidirectional"))
      (node (ref "J4") (pin "B7") (pinfunction "DN2_B7") (pintype "bidirectional"))
    )
    (net (code "6") (name "DP") (class "Default")
      (node (ref "D2") (pin "3") (pinfunction "I/O2_1_3") (pintype "bidirectional"))
      (node (ref "J4") (pin "A6") (pinfunction "DP1_A6") (pintype "bidirectional"))
      (node (ref "J4") (pin "B6") (pinfunction "DP2_B6") (pintype "bidirectional"))
    )
    (net (code "7") (name "EPD_3V3") (class "Default")
      (node (ref "C1-EP-DR") (pin "1") (pinfunction "1_1") (pintype "passive"))
      (node (ref "EPD_C5") (pin "1") (pinfunction "1_1") (pintype "passive"))
      (node (ref "J1") (pin "15") (pinfunction "15_15") (pintype "bidirectional"))
      (node (ref "J1") (pin "16") (pinfunction "16_16") (pintype "bidirectional"))
      (node (ref "L4") (pin "2") (pinfunction "2_2") (pintype "passive"))
      (node (ref "Q1") (pin "3") (pinfunction "D_3") (pintype "bidirectional"))
    )
    (net (code "8") (name "EPD_BUSY") (class "Default")
      (node (ref "J1") (pin "9") (pinfunction "9_9") (pintype "bidirectional"))
      (node (ref "U1") (pin "P$AD12") (pinfunction "P0.17_P$AD12") (pintype "bidirectional"))
    )
    (net (code "9") (name "EPD_CS") (class "Default")
      (node (ref "J1") (pin "12") (pinfunction "12_12") (pintype "bidirectional"))
      (node (ref "U1") (pin "P$K2") (pinfunction "P0.05/AIN3_P$K2") (pintype "bidirectional"))
    )
    (net (code "10") (name "EPD_DC") (class "Default")
      (node (ref "J1") (pin "11") (pinfunction "11_11") (pintype "bidirectional"))
      (node (ref "U1") (pin "P$AD10") (pinfunction "P0.15_P$AD10") (pintype "bidirectional"))
    )
    (net (code "11") (name "EPD_RST") (class "Default")
      (node (ref "J1") (pin "10") (pinfunction "10_10") (pintype "bidirectional"))
      (node (ref "U1") (pin "P$AC11") (pinfunction "P0.16_P$AC11") (pintype "bidirectional"))
    )
    (net (code "12") (name "GDR") (class "Default")
      (node (ref "J1") (pin "2") (pinfunction "2_2") (pintype "bidirectional"))
      (node (ref "Q3") (pin "1") (pinfunction "G_1") (pintype "bidirectional"))
      (node (ref "R2_EP_DR") (pin "2") (pinfunction "2_2") (pintype "bidirectional"))
    )
    (net (code "13") (name "GND") (class "Default")
      (node (ref "C1") (pin "2") (pinfunction "2_2") (pintype "passive"))
      (node (ref "C1-EP-DR") (pin "2") (pinfunction "2_2") (pintype "passive"))
      (node (ref "C10") (pin "1") (pinfunction "1_1") (pintype "passive"))
      (node (ref "C11") (pin "1") (pinfunction "1_1") (pintype "passive"))
      (node (ref "C12") (pin "2") (pinfunction "2_2") (pintype "passive"))
      (node (ref "C13") (pin "1") (pinfunction "1_1") (pintype "passive"))
      (node (ref "C14") (pin "1") (pinfunction "1_1") (pintype "passive"))
      (node (ref "C15") (pin "2") (pinfunction "2_2") (pintype "passive"))
      (node (ref "C16") (pin "2") (pinfunction "2_2") (pintype "passive"))
      (node (ref "C17") (pin "1") (pinfunction "1_1") (pintype "passive"))
      (node (ref "C18") (pin "1") (pinfunction "1_1") (pintype "passive"))
      (node (ref "C19") (pin "2") (pinfunction "2_2") (pintype "passive"))
      (node (ref "C2") (pin "2") (pinfunction "2_2") (pintype "passive"))
      (node (ref "C20") (pin "2") (pinfunction "2_2") (pintype "passive"))
      (node (ref "C21") (pin "2") (pinfunction "2_2") (pintype "passive"))
      (node (ref "C22") (pin "2") (pinfunction "2_2") (pintype "passive"))
      (node (ref "C23") (pin "1") (pinfunction "1_1") (pintype "passive"))
      (node (ref "C24") (pin "1") (pinfunction "1_1") (pintype "passive"))
      (node (ref "C25") (pin "2") (pinfunction "2_2") (pintype "passive"))
      (node (ref "C27") (pin "2") (pinfunction "2_2") (pintype "passive"))
      (node (ref "C29") (pin "2") (pinfunction "2_2") (pintype "passive"))
      (node (ref "C3") (pin "2") (pinfunction "2_2") (pintype "passive"))
      (node (ref "C30") (pin "2") (pinfunction "2_2") (pintype "passive"))
      (node (ref "C31") (pin "2") (pinfunction "2_2") (pintype "passive"))
      (node (ref "C32") (pin "2") (pinfunction "2_2") (pintype "passive"))
      (node (ref "C33") (pin "2") (pinfunction "2_2") (pintype "passive"))
      (node (ref "C34") (pin "2") (pinfunction "2_2") (pintype "passive"))
      (node (ref "C37") (pin "2") (pinfunction "2_2") (pintype "passive"))
      (node (ref "C38") (pin "2") (pinfunction "2_2") (pintype "passive"))
      (node (ref "C39") (pin "2") (pinfunction "2_2") (pintype "passive"))
      (node (ref "C4") (pin "2") (pinfunction "2_2") (pintype "passive"))
      (node (ref "C42") (pin "2") (pinfunction "2_2") (pintype "passive"))
      (node (ref "C43") (pin "2") (pinfunction "2_2") (pintype "passive"))
      (node (ref "C5") (pin "1") (pinfunction "1_1") (pintype "passive"))
      (node (ref "C6") (pin "2") (pinfunction "2_2") (pintype "passive"))
      (node (ref "C7") (pin "2") (pinfunction "2_2") (pintype "passive"))
      (node (ref "C8") (pin "2") (pinfunction "2_2") (pintype "passive"))
      (node (ref "C9") (pin "2") (pinfunction "2_2") (pintype "passive"))
      (node (ref "D2") (pin "2") (pinfunction "GND_2") (pintype "bidirectional"))
      (node (ref "D4") (pin "1") (pinfunction "K_1") (pintype "bidirectional"))
      (node (ref "EPD_C1") (pin "2") (pinfunction "2_2") (pintype "passive"))
      (node (ref "EPD_C10") (pin "2") (pinfunction "2_2") (pintype "passive"))
      (node (ref "EPD_C11") (pin "2") (pinfunction "2_2") (pintype "passive"))
      (node (ref "EPD_C12") (pin "2") (pinfunction "2_2") (pintype "passive"))
      (node (ref "EPD_C2") (pin "2") (pinfunction "2_2") (pintype "passive"))
      (node (ref "EPD_C5") (pin "2") (pinfunction "2_2") (pintype "passive"))
      (node (ref "EPD_C6") (pin "2") (pinfunction "2_2") (pintype "passive"))
      (node (ref "EPD_C7") (pin "2") (pinfunction "2_2") (pintype "passive"))
      (node (ref "EPD_C8") (pin "2") (pinfunction "2_2") (pintype "passive"))
      (node (ref "EPD_C9") (pin "2") (pinfunction "2_2") (pintype "passive"))
      (node (ref "IC1") (pin "D2") (pinfunction "GND_D2") (pintype "bidirectional"))
      (node (ref "IC2") (pin "B1") (pinfunction "IN/TRIG_B1") (pintype "bidirectional"))
      (node (ref "IC2") (pin "B3") (pinfunction "GND_B3") (pintype "bidirectional"))
      (node (ref "IC3") (pin "8") (pinfunction "GNDIO_8") (pintype "bidirectional"))
      (node (ref "IC3") (pin "9") (pinfunction "GND_9") (pintype "bidirectional"))
      (node (ref "IC9") (pin "B1") (pinfunction "VSEL_B1") (pintype "bidirectional"))
      (node (ref "IC9") (pin "C1") (pinfunction "AGND_C1") (pintype "bidirectional"))
      (node (ref "IC9") (pin "C2") (pinfunction "PGND_1_C2") (pintype "bidirectional"))
      (node (ref "IC9") (pin "C3") (pinfunction "PGND_2_C3") (pintype "bidirectional"))
      (node (ref "J1") (pin "17") (pinfunction "17_17") (pintype "bidirectional"))
      (node (ref "J1") (pin "8") (pinfunction "8_8") (pintype "bidirectional"))
      (node (ref "J1") (pin "MP1") (pinfunction "MP1_MP1") (pintype "bidirectional"))
      (node (ref "J1") (pin "MP2") (pinfunction "MP2_MP2") (pintype "bidirectional"))
      (node (ref "J2") (pin "3") (pinfunction "3_3") (pintype "bidirectional"))
      (node (ref "J2") (pin "5") (pinfunction "5_5") (pintype "bidirectional"))
      (node (ref "J4") (pin "A12_B1") (pinfunction "GND_A12_B1") (pintype "power_in"))
      (node (ref "J4") (pin "A1_B12") (pinfunction "GND_A1_B12") (pintype "power_in"))
      (node (ref "J4") (pin "SH1") (pinfunction "SHIELD_SH1") (pintype "passive"))
      (node (ref "J4") (pin "SH2") (pinfunction "SHIELD_SH2") (pintype "passive"))
      (node (ref "J4") (pin "SH3") (pinfunction "SHIELD_SH3") (pintype "passive"))
      (node (ref "J4") (pin "SH4") (pinfunction "SHIELD_SH4") (pintype "passive"))
      (node (ref "R1_USB") (pin "1") (pinfunction "1_1") (pintype "bidirectional"))
      (node (ref "R2_EP_DR") (pin "1") (pinfunction "1_1") (pintype "bidirectional"))
      (node (ref "R2_USB") (pin "2") (pinfunction "2_2") (pintype "bidirectional"))
      (node (ref "R3") (pin "1") (pinfunction "1_1") (pintype "bidirectional"))
      (node (ref "R9") (pin "1") (pinfunction "1_1") (pintype "bidirectional"))
      (node (ref "R_TYPE_SEL") (pin "1") (pinfunction "1_1") (pintype "bidirectional"))
      (node (ref "SJ1") (pin "1") (pinfunction "1_1") (pintype "passive"))
      (node (ref "SW_DN") (pin "1") (pinfunction "1_1") (pintype "passive"))
      (node (ref "SW_ENT") (pin "1") (pinfunction "1_1") (pintype "passive"))
      (node (ref "SW_UP") (pin "1") (pinfunction "1_1") (pintype "passive"))
      (node (ref "TP_BAT_GND") (pin "TP") (pinfunction "TP_TP") (pintype "input"))
      (node (ref "TP_GND") (pin "TP") (pinfunction "TP_TP") (pintype "input"))
      (node (ref "U1") (pin "P$74") (pinfunction "VSS_PAD_P$74") (pintype "bidirectional"))
      (node (ref "U1") (pin "P$75") (pinfunction "VSS_PAD_P$75") (pintype "bidirectional"))
      (node (ref "U1") (pin "P$76") (pinfunction "VSS_PAD_P$76") (pintype "bidirectional"))
      (node (ref "U1") (pin "P$77") (pinfunction "VSS_PAD_P$77") (pintype "bidirectional"))
      (node (ref "U1") (pin "P$78") (pinfunction "VSS_PAD_P$78") (pintype "bidirectional"))
      (node (ref "U1") (pin "P$79") (pinfunction "VSS_PAD_P$79") (pintype "bidirectional"))
      (node (ref "U1") (pin "P$80") (pinfunction "VSS_PAD_P$80") (pintype "bidirectional"))
      (node (ref "U1") (pin "P$81") (pinfunction "VSS_PAD_P$81") (pintype "bidirectional"))
      (node (ref "U1") (pin "P$82") (pinfunction "VSS_PAD_P$82") (pintype "bidirectional"))
      (node (ref "U1") (pin "P$83") (pinfunction "VSS_PAD_P$83") (pintype "bidirectional"))
      (node (ref "U1") (pin "P$84") (pinfunction "VSS_PAD_P$84") (pintype "bidirectional"))
      (node (ref "U1") (pin "P$85") (pinfunction "VSS_PAD_P$85") (pintype "bidirectional"))
      (node (ref "U1") (pin "P$86") (pinfunction "VSS_PAD_P$86") (pintype "bidirectional"))
      (node (ref "U1") (pin "P$87") (pinfunction "VSS_PAD_P$87") (pintype "bidirectional"))
      (node (ref "U1") (pin "P$88") (pinfunction "VSS_PAD_P$88") (pintype "bidirectional"))
      (node (ref "U1") (pin "P$89") (pinfunction "VSS_PAD_P$89") (pintype "bidirectional"))
      (node (ref "U1") (pin "P$90") (pinfunction "VSS_PAD_P$90") (pintype "bidirectional"))
      (node (ref "U1") (pin "P$B7") (pinfunction "VSS_P$B7") (pintype "power_in"))
      (node (ref "U1") (pin "P$F23") (pinfunction "VSS_PA_P$F23") (pintype "bidirectional"))
      (node (ref "U3") (pin "1") (pinfunction "CTG_1") (pintype "power_in"))
      (node (ref "U3") (pin "4") (pinfunction "GND_4") (pintype "power_in"))
      (node (ref "U3") (pin "6") (pinfunction "QSTRT_6") (pintype "input"))
      (node (ref "U3") (pin "9") (pinfunction "EP_9") (pintype "power_in"))
      (node (ref "X1") (pin "2") (pinfunction "2_2") (pintype "passive"))
      (node (ref "X1") (pin "4") (pinfunction "4_4") (pintype "passive"))
    )
    (net (code "14") (name "HAPTIC_EN") (class "Default")
      (node (ref "IC2") (pin "A1") (pinfunction "EN_A1") (pintype "bidirectional"))
      (node (ref "U1") (pin "P$U1") (pinfunction "P0.12_P$U1") (pintype "bidirectional"))
    )
    (net (code "15") (name "IMU_INT1") (class "Default")
      (node (ref "IC3") (pin "5") (pinfunction "INT1_5") (pintype "bidirectional"))
      (node (ref "U1") (pin "P$N1") (pinfunction "P0.08_P$N1") (pintype "bidirectional"))
    )
    (net (code "16") (name "IMU_INT2") (class "Default")
      (node (ref "IC3") (pin "6") (pinfunction "INT2_6") (pintype "bidirectional"))
      (node (ref "U1") (pin "P$P2") (pinfunction "P1.08_P$P2") (pintype "bidirectional"))
    )
    (net (code "17") (name "LX1") (class "Default")
      (node (ref "IC9") (pin "B2") (pinfunction "SW1_1_B2") (pintype "bidirectional"))
      (node (ref "IC9") (pin "B3") (pinfunction "SW1_2_B3") (pintype "bidirectional"))
      (node (ref "L7") (pin "1") (pinfunction "1_1") (pintype "bidirectional"))
    )
    (net (code "18") (name "LX2") (class "Default")
      (node (ref "IC9") (pin "D2") (pinfunction "SW2_1_D2") (pintype "bidirectional"))
      (node (ref "IC9") (pin "D3") (pinfunction "SW2_2_D3") (pintype "bidirectional"))
      (node (ref "L7") (pin "2") (pinfunction "2_2") (pintype "bidirectional"))
    )
    (net (code "19") (name "MOSI") (class "Default")
      (node (ref "J1") (pin "14") (pinfunction "14_14") (pintype "bidirectional"))
      (node (ref "U1") (pin "P$B13") (pinfunction "P0.03/AIN1_P$B13") (pintype "bidirectional"))
    )
    (net (code "20") (name "Net-(ANT1-FEED)") (class "Default")
      (node (ref "ANT1") (pin "1") (pinfunction "FEED_1") (pintype "input"))
      (node (ref "C22") (pin "1") (pinfunction "1_1") (pintype "passive"))
      (node (ref "C4") (pin "1") (pinfunction "1_1") (pintype "passive"))
      (node (ref "L1") (pin "2") (pinfunction "2_2") (pintype "passive"))
    )
    (net (code "21") (name "Net-(D3-K)") (class "Default")
      (node (ref "C1-EP-DR1") (pin "1") (pinfunction "1_1") (pintype "passive"))
      (node (ref "D3") (pin "1") (pinfunction "K_1") (pintype "bidirectional"))
      (node (ref "D4") (pin "2") (pinfunction "A_2") (pintype "bidirectional"))
    )
    (net (code "22") (name "Net-(D5-A)") (class "Default")
      (node (ref "C1-EP-DR1") (pin "2") (pinfunction "2_2") (pintype "passive"))
      (node (ref "D5") (pin "2") (pinfunction "A_2") (pintype "bidirectional"))
      (node (ref "L4") (pin "1") (pinfunction "1_1") (pintype "passive"))
      (node (ref "Q3") (pin "3") (pinfunction "D_3") (pintype "bidirectional"))
    )
    (net (code "23") (name "Net-(EPD_C1-Pad1)") (class "Default")
      (node (ref "EPD_C1") (pin "1") (pinfunction "1_1") (pintype "passive"))
      (node (ref "J1") (pin "5") (pinfunction "5_5") (pintype "bidirectional"))
    )
    (net (code "24") (name "Net-(EPD_C2-Pad1)") (class "Default")
      (node (ref "EPD_C2") (pin "1") (pinfunction "1_1") (pintype "passive"))
      (node (ref "J1") (pin "4") (pinfunction "4_4") (pintype "bidirectional"))
    )
    (net (code "25") (name "Net-(EPD_C6-Pad1)") (class "Default")
      (node (ref "EPD_C6") (pin "1") (pinfunction "1_1") (pintype "passive"))
      (node (ref "J1") (pin "18") (pinfunction "18_18") (pintype "bidirectional"))
    )
    (net (code "26") (name "Net-(EPD_C7-Pad1)") (class "Default")
      (node (ref "EPD_C7") (pin "1") (pinfunction "1_1") (pintype "passive"))
      (node (ref "J1") (pin "19") (pinfunction "19_19") (pintype "bidirectional"))
    )
    (net (code "27") (name "Net-(EPD_C8-Pad1)") (class "Default")
      (node (ref "EPD_C8") (pin "1") (pinfunction "1_1") (pintype "passive"))
      (node (ref "J1") (pin "20") (pinfunction "20_20") (pintype "bidirectional"))
    )
    (net (code "28") (name "Net-(EPD_C10-Pad1)") (class "Default")
      (node (ref "EPD_C10") (pin "1") (pinfunction "1_1") (pintype "passive"))
      (node (ref "J1") (pin "22") (pinfunction "22_22") (pintype "bidirectional"))
    )
    (net (code "29") (name "Net-(EPD_C12-Pad1)") (class "Default")
      (node (ref "EPD_C12") (pin "1") (pinfunction "1_1") (pintype "passive"))
      (node (ref "J1") (pin "24") (pinfunction "24_24") (pintype "bidirectional"))
    )
    (net (code "30") (name "Net-(IC1-TS{slash}MR)") (class "Default")
      (node (ref "IC1") (pin "D1") (pinfunction "TS/MR_D1") (pintype "bidirectional"))
      (node (ref "R9") (pin "2") (pinfunction "2_2") (pintype "bidirectional"))
    )
    (net (code "31") (name "Net-(IC2-REG)") (class "Default")
      (node (ref "C32") (pin "1") (pinfunction "1_1") (pintype "passive"))
      (node (ref "IC2") (pin "A2") (pinfunction "REG_A2") (pintype "bidirectional"))
    )
    (net (code "32") (name "Net-(IC3-SDO)") (class "Default")
      (node (ref "IC3") (pin "1") (pinfunction "SDO_1") (pintype "bidirectional"))
      (node (ref "R3") (pin "2") (pinfunction "2_2") (pintype "bidirectional"))
    )
    (net (code "33") (name "Net-(IC9-SCL)") (class "Default")
      (node (ref "IC9") (pin "D1") (pinfunction "SCL_D1") (pintype "bidirectional"))
      (node (ref "R4") (pin "2") (pinfunction "2_2") (pintype "bidirectional"))
    )
    (net (code "34") (name "Net-(IC9-SDA)") (class "Default")
      (node (ref "IC9") (pin "E1") (pinfunction "SDA_E1") (pintype "bidirectional"))
      (node (ref "R2") (pin "2") (pinfunction "2_2") (pintype "bidirectional"))
    )
    (net (code "35") (name "Net-(J4-CC1)") (class "Default")
      (node (ref "J4") (pin "A5") (pinfunction "CC1_A5") (pintype "bidirectional"))
      (node (ref "R1_USB") (pin "2") (pinfunction "2_2") (pintype "bidirectional"))
    )
    (net (code "36") (name "Net-(J4-CC2)") (class "Default")
      (node (ref "J4") (pin "B5") (pinfunction "CC2_B5") (pintype "bidirectional"))
      (node (ref "R2_USB") (pin "1") (pinfunction "1_1") (pintype "bidirectional"))
    )
    (net (code "37") (name "Net-(L2-Pad1)") (class "Default")
      (node (ref "L2") (pin "1") (pinfunction "1_1") (pintype "passive"))
      (node (ref "L3") (pin "2") (pinfunction "2_2") (pintype "passive"))
    )
    (net (code "38") (name "Net-(R1_EP_DR-Pad1)") (class "Default")
      (node (ref "R1_EP_DR") (pin "1") (pinfunction "1_1") (pintype "bidirectional"))
      (node (ref "R_TYPE_SEL") (pin "2") (pinfunction "2_2") (pintype "bidirectional"))
      (node (ref "SJ1") (pin "2") (pinfunction "2_2") (pintype "passive"))
    )
    (net (code "39") (name "Net-(U1-ANT)") (class "Default")
      (node (ref "C3") (pin "1") (pinfunction "1_1") (pintype "passive"))
      (node (ref "L1") (pin "1") (pinfunction "1_1") (pintype "passive"))
      (node (ref "U1") (pin "P$H23") (pinfunction "ANT_P$H23") (pintype "bidirectional"))
    )
    (net (code "40") (name "Net-(U1-DCC)") (class "Default")
      (node (ref "L2") (pin "2") (pinfunction "2_2") (pintype "passive"))
      (node (ref "U1") (pin "P$B3") (pinfunction "DCC_P$B3") (pintype "output"))
    )
    (net (code "41") (name "Net-(U1-DEC1)") (class "Default")
      (node (ref "C5") (pin "2") (pinfunction "2_2") (pintype "passive"))
      (node (ref "U1") (pin "P$C1") (pinfunction "DEC1_P$C1") (pintype "power_in"))
    )
    (net (code "42") (name "Net-(U1-DEC2)") (class "Default")
      (node (ref "C13") (pin "2") (pinfunction "2_2") (pintype "passive"))
      (node (ref "U1") (pin "P$A18") (pinfunction "DEC2_P$A18") (pintype "bidirectional"))
    )
    (net (code "43") (name "Net-(U1-DEC3)") (class "Default")
      (node (ref "C11") (pin "2") (pinfunction "2_2") (pintype "passive"))
      (node (ref "U1") (pin "P$D23") (pinfunction "DEC3_P$D23") (pintype "bidirectional"))
    )
    (net (code "44") (name "Net-(U1-DEC3V3)") (class "Default")
      (node (ref "C20") (pin "1") (pinfunction "1_1") (pintype "passive"))
      (node (ref "U1") (pin "P$AC5") (pinfunction "DEC3V3_P$AC5") (pintype "bidirectional"))
    )
    (net (code "45") (name "Net-(U1-DEC4)") (class "Default")
      (node (ref "C10") (pin "2") (pinfunction "2_2") (pintype "passive"))
      (node (ref "C15") (pin "1") (pinfunction "1_1") (pintype "passive"))
      (node (ref "C16") (pin "1") (pinfunction "1_1") (pintype "passive"))
      (node (ref "L3") (pin "1") (pinfunction "1_1") (pintype "passive"))
      (node (ref "U1") (pin "P$B5") (pinfunction "DEC4_P$B5") (pintype "power_in"))
      (node (ref "U1") (pin "P$E24") (pinfunction "DEC6_P$E24") (pintype "bidirectional"))
    )
    (net (code "46") (name "Net-(U1-DEC5)") (class "Default")
      (node (ref "C9") (pin "1") (pinfunction "1_1") (pintype "passive"))
      (node (ref "U1") (pin "P$N24") (pinfunction "DEC5_P$N24") (pintype "bidirectional"))
    )
    (net (code "47") (name "Net-(U1-P0.00{slash}XL1)") (class "Default")
      (node (ref "C17") (pin "2") (pinfunction "2_2") (pintype "passive"))
      (node (ref "U1") (pin "P$D2") (pinfunction "P0.00/XL1_P$D2") (pintype "bidirectional"))
      (node (ref "X2") (pin "2") (pinfunction "2_2") (pintype "passive"))
    )
    (net (code "48") (name "Net-(U1-P0.01{slash}XL2)") (class "Default")
      (node (ref "C18") (pin "2") (pinfunction "2_2") (pintype "passive"))
      (node (ref "U1") (pin "P$F2") (pinfunction "P0.01/XL2_P$F2") (pintype "bidirectional"))
      (node (ref "X2") (pin "1") (pinfunction "1_1") (pintype "passive"))
    )
    (net (code "49") (name "Net-(U1-XC1)") (class "Default")
      (node (ref "C1") (pin "1") (pinfunction "1_1") (pintype "passive"))
      (node (ref "U1") (pin "P$B24") (pinfunction "XC1_P$B24") (pintype "input"))
      (node (ref "X1") (pin "1") (pinfunction "1_1") (pintype "passive"))
    )
    (net (code "50") (name "Net-(U1-XC2)") (class "Default")
      (node (ref "C2") (pin "1") (pinfunction "1_1") (pintype "passive"))
      (node (ref "U1") (pin "P$A23") (pinfunction "XC2_P$A23") (pintype "output"))
      (node (ref "X1") (pin "3") (pinfunction "3_3") (pintype "passive"))
    )
    (net (code "51") (name "OUT+") (class "Default")
      (node (ref "IC2") (pin "A3") (pinfunction "OUT+_A3") (pintype "bidirectional"))
      (node (ref "TP_OP") (pin "TP") (pinfunction "TP_TP") (pintype "input"))
    )
    (net (code "52") (name "OUT-") (class "Default")
      (node (ref "IC2") (pin "C3") (pinfunction "OUT-_C3") (pintype "bidirectional"))
      (node (ref "TP_ON") (pin "TP") (pinfunction "TP_TP") (pintype "input"))
    )
    (net (code "53") (name "P0.04") (class "Default")
      (node (ref "U1") (pin "P$J1") (pinfunction "P0.04/AIN2_P$J1") (pintype "bidirectional"))
    )
    (net (code "54") (name "P0.09") (class "Default")
      (node (ref "U1") (pin "P$L24") (pinfunction "P0.09/NFC1_P$L24") (pintype "bidirectional"))
    )
    (net (code "55") (name "P0.13") (class "Default")
      (node (ref "C30") (pin "1") (pinfunction "1_1") (pintype "passive"))
      (node (ref "R5") (pin "1") (pinfunction "1_1") (pintype "bidirectional"))
      (node (ref "SW_UP") (pin "2") (pinfunction "2_2") (pintype "passive"))
      (node (ref "U1") (pin "P$AD8") (pinfunction "P0.13_P$AD8") (pintype "bidirectional"))
    )
    (net (code "56") (name "P0.14") (class "Default")
      (node (ref "C31") (pin "1") (pinfunction "1_1") (pintype "passive"))
      (node (ref "R8") (pin "1") (pinfunction "1_1") (pintype "bidirectional"))
      (node (ref "SW_ENT") (pin "2") (pinfunction "2_2") (pintype "passive"))
      (node (ref "U1") (pin "P$AC9") (pinfunction "P0.14_P$AC9") (pintype "bidirectional"))
    )
    (net (code "57") (name "P0.19") (class "Default")
      (node (ref "U1") (pin "P$AC15") (pinfunction "P0.19_P$AC15") (pintype "bidirectional"))
    )
    (net (code "58") (name "P0.20") (class "Default")
      (node (ref "U1") (pin "P$AD16") (pinfunction "P0.20_P$AD16") (pintype "bidirectional"))
    )
    (net (code "59") (name "P0.21") (class "Default")
      (node (ref "U1") (pin "P$AC17") (pinfunction "P0.21_P$AC17") (pintype "bidirectional"))
    )
    (net (code "60") (name "P0.22") (class "Default")
      (node (ref "U1") (pin "P$AD18") (pinfunction "P0.22_P$AD18") (pintype "bidirectional"))
    )
    (net (code "61") (name "P0.23") (class "Default")
      (node (ref "U1") (pin "P$AC19") (pinfunction "P0.23_P$AC19") (pintype "bidirectional"))
    )
    (net (code "62") (name "P0.24") (class "Default")
      (node (ref "U1") (pin "P$AD20") (pinfunction "P0.24_P$AD20") (pintype "bidirectional"))
    )
    (net (code "63") (name "P0.25") (class "Default")
      (node (ref "U1") (pin "P$AC21") (pinfunction "P0.25_P$AC21") (pintype "bidirectional"))
    )
    (net (code "64") (name "P0.26") (class "Default")
      (node (ref "U1") (pin "P$G1") (pinfunction "P0.26_P$G1") (pintype "bidirectional"))
    )
    (net (code "65") (name "P0.27") (class "Default")
      (node (ref "U1") (pin "P$H2") (pinfunction "P0.27_P$H2") (pintype "bidirectional"))
    )
    (net (code "66") (name "P0.28") (class "Default")
      (node (ref "U1") (pin "P$B11") (pinfunction "P0.28/AIN4_P$B11") (pintype "bidirectional"))
    )
    (net (code "67") (name "P0.29") (class "Default")
      (node (ref "U1") (pin "P$A10") (pinfunction "P0.29/AIN5_P$A10") (pintype "bidirectional"))
    )
    (net (code "68") (name "P0.30") (class "Default")
      (node (ref "U1") (pin "P$B9") (pinfunction "P0.30/AIN6_P$B9") (pintype "bidirectional"))
    )
    (net (code "69") (name "P0.31") (class "Default")
      (node (ref "U1") (pin "P$A8") (pinfunction "P0.31/AIN7_P$A8") (pintype "bidirectional"))
    )
    (net (code "70") (name "P1.01") (class "Default")
      (node (ref "Q1") (pin "1") (pinfunction "G_1") (pintype "bidirectional"))
      (node (ref "R_PWR_EPD") (pin "1") (pinfunction "1_1") (pintype "bidirectional"))
      (node (ref "U1") (pin "P$Y23") (pinfunction "P1.01_P$Y23") (pintype "bidirectional"))
    )
    (net (code "71") (name "P1.02") (class "Default")
      (node (ref "C29") (pin "1") (pinfunction "1_1") (pintype "passive"))
      (node (ref "R7") (pin "1") (pinfunction "1_1") (pintype "bidirectional"))
      (node (ref "SW_DN") (pin "2") (pinfunction "2_2") (pintype "passive"))
      (node (ref "U1") (pin "P$W24") (pinfunction "P1.02_P$W24") (pintype "bidirectional"))
    )
    (net (code "72") (name "P1.03") (class "Default")
      (node (ref "U1") (pin "P$V23") (pinfunction "P1.03_P$V23") (pintype "bidirectional"))
    )
    (net (code "73") (name "P1.04") (class "Default")
      (node (ref "U1") (pin "P$U24") (pinfunction "P1.04_P$U24") (pintype "bidirectional"))
    )
    (net (code "74") (name "P1.05") (class "Default")
      (node (ref "U1") (pin "P$T23") (pinfunction "P1.05_P$T23") (pintype "bidirectional"))
    )
    (net (code "75") (name "P1.06") (class "Default")
      (node (ref "U1") (pin "P$R24") (pinfunction "P1.06_P$R24") (pintype "bidirectional"))
    )
    (net (code "76") (name "P1.07") (class "Default")
      (node (ref "U1") (pin "P$P23") (pinfunction "P1.07_P$P23") (pintype "bidirectional"))
    )
    (net (code "77") (name "P1.09") (class "Default")
      (node (ref "U1") (pin "P$R1") (pinfunction "P1.09_P$R1") (pintype "bidirectional"))
    )
    (net (code "78") (name "P1.10") (class "Default")
      (node (ref "U1") (pin "P$A20") (pinfunction "P1.10_P$A20") (pintype "bidirectional"))
    )
    (net (code "79") (name "P1.11") (class "Default")
      (node (ref "U1") (pin "P$B19") (pinfunction "P1.11_P$B19") (pintype "bidirectional"))
    )
    (net (code "80") (name "P1.12") (class "Default")
      (node (ref "U1") (pin "P$B17") (pinfunction "P1.12_P$B17") (pintype "bidirectional"))
    )
    (net (code "81") (name "P1.13") (class "Default")
      (node (ref "U1") (pin "P$A16") (pinfunction "P1.13_P$A16") (pintype "bidirectional"))
    )
    (net (code "82") (name "P1.14") (class "Default")
      (node (ref "U1") (pin "P$B15") (pinfunction "P1.14_P$B15") (pintype "bidirectional"))
    )
    (net (code "83") (name "P1.15") (class "Default")
      (node (ref "U1") (pin "P$A14") (pinfunction "P1.15_P$A14") (pintype "bidirectional"))
    )
    (net (code "84") (name "PMIC_INT") (class "Default")
      (node (ref "IC1") (pin "A1") (pinfunction "~{INT}_A1") (pintype "bidirectional"))
      (node (ref "U1") (pin "P$T2") (pinfunction "P0.11_P$T2") (pintype "bidirectional"))
    )
    (net (code "85") (name "PREVGH") (class "Default")
      (node (ref "D5") (pin "1") (pinfunction "K_1") (pintype "bidirectional"))
      (node (ref "EPD_C9") (pin "1") (pinfunction "1_1") (pintype "passive"))
      (node (ref "J1") (pin "21") (pinfunction "21_21") (pintype "bidirectional"))
    )
    (net (code "86") (name "PREVGL") (class "Default")
      (node (ref "D3") (pin "2") (pinfunction "A_2") (pintype "bidirectional"))
      (node (ref "EPD_C11") (pin "1") (pinfunction "1_1") (pintype "passive"))
      (node (ref "J1") (pin "23") (pinfunction "23_23") (pintype "bidirectional"))
    )
    (net (code "87") (name "RESE") (class "Default")
      (node (ref "J1") (pin "3") (pinfunction "3_3") (pintype "bidirectional"))
      (node (ref "Q3") (pin "2") (pinfunction "S_2") (pintype "bidirectional"))
      (node (ref "R1_EP_DR") (pin "2") (pinfunction "2_2") (pintype "bidirectional"))
    )
    (net (code "88") (name "RESET") (class "Default")
      (node (ref "J2") (pin "6") (pinfunction "6_6") (pintype "bidirectional"))
      (node (ref "TP_RESET\\") (pin "TP") (pinfunction "TP_TP") (pintype "input"))
      (node (ref "U1") (pin "P$AC13") (pinfunction "P0.18/RESET_P$AC13") (pintype "bidirectional"))
    )
    (net (code "89") (name "SCK") (class "Default")
      (node (ref "J1") (pin "13") (pinfunction "13_13") (pintype "bidirectional"))
      (node (ref "U1") (pin "P$A12") (pinfunction "P0.02/AIN0_P$A12") (pintype "bidirectional"))
    )
    (net (code "90") (name "SCL") (class "Default")
      (node (ref "IC1") (pin "B1") (pinfunction "SCL_B1") (pintype "bidirectional"))
      (node (ref "IC2") (pin "C1") (pinfunction "SCL_C1") (pintype "bidirectional"))
      (node (ref "IC3") (pin "12") (pinfunction "SCX_12") (pintype "bidirectional"))
      (node (ref "R17") (pin "2") (pinfunction "2_2") (pintype "bidirectional"))
      (node (ref "R4") (pin "1") (pinfunction "1_1") (pintype "bidirectional"))
      (node (ref "TP_SCL") (pin "TP") (pinfunction "TP_TP") (pintype "input"))
      (node (ref "U1") (pin "P$M2") (pinfunction "P0.07_P$M2") (pintype "bidirectional"))
      (node (ref "U3") (pin "7") (pinfunction "SCL_7") (pintype "input"))
    )
    (net (code "91") (name "SDA") (class "Default")
      (node (ref "IC1") (pin "C1") (pinfunction "SDA_C1") (pintype "bidirectional"))
      (node (ref "IC2") (pin "B2") (pinfunction "SDA_B2") (pintype "bidirectional"))
      (node (ref "IC3") (pin "2") (pinfunction "SDX_2") (pintype "bidirectional"))
      (node (ref "R18") (pin "2") (pinfunction "2_2") (pintype "bidirectional"))
      (node (ref "R2") (pin "1") (pinfunction "1_1") (pintype "bidirectional"))
      (node (ref "TP_SDA") (pin "TP") (pinfunction "TP_TP") (pintype "input"))
      (node (ref "U1") (pin "P$L1") (pinfunction "P0.06_P$L1") (pintype "bidirectional"))
      (node (ref "U3") (pin "8") (pinfunction "SDA_8") (pintype "bidirectional"))
    )
    (net (code "92") (name "SWDCLK") (class "Default")
      (node (ref "J2") (pin "4") (pinfunction "4_4") (pintype "bidirectional"))
      (node (ref "TP_SWDCLK") (pin "TP") (pinfunction "TP_TP") (pintype "input"))
      (node (ref "U1") (pin "P$AA24") (pinfunction "SWDCLK_P$AA24") (pintype "input"))
    )
    (net (code "93") (name "SWDIO") (class "Default")
      (node (ref "J2") (pin "2") (pinfunction "2_2") (pintype "bidirectional"))
      (node (ref "TP_SWDIO") (pin "TP") (pinfunction "TP_TP") (pintype "input"))
      (node (ref "U1") (pin "P$AC24") (pinfunction "SWDIO_P$AC24") (pintype "bidirectional"))
    )
    (net (code "94") (name "SWO") (class "Default")
      (node (ref "TP_SWO") (pin "TP") (pinfunction "TP_TP") (pintype "input"))
      (node (ref "U1") (pin "P$AD22") (pinfunction "P1.00_P$AD22") (pintype "bidirectional"))
    )
    (net (code "95") (name "VBAT") (class "Default")
      (node (ref "C27") (pin "1") (pinfunction "1_1") (pintype "passive"))
      (node (ref "C37") (pin "1") (pinfunction "1_1") (pintype "passive"))
      (node (ref "IC1") (pin "C2") (pinfunction "BAT_C2") (pintype "bidirectional"))
      (node (ref "TP_VBAT") (pin "TP") (pinfunction "TP_TP") (pintype "input"))
      (node (ref "U3") (pin "2") (pinfunction "CELL_2") (pintype "power_in"))
      (node (ref "U3") (pin "3") (pinfunction "VDD_3") (pintype "power_in"))
    )
    (net (code "96") (name "VBUS") (class "Default")
      (node (ref "C21") (pin "1") (pinfunction "1_1") (pintype "passive"))
      (node (ref "C38") (pin "1") (pinfunction "1_1") (pintype "passive"))
      (node (ref "C42") (pin "1") (pinfunction "1_1") (pintype "passive"))
      (node (ref "C43") (pin "1") (pinfunction "1_1") (pintype "passive"))
      (node (ref "D2") (pin "5") (pinfunction "VBUS_5") (pintype "bidirectional"))
      (node (ref "IC1") (pin "A2") (pinfunction "IN_A2") (pintype "bidirectional"))
      (node (ref "J4") (pin "A4_B9") (pinfunction "VBUS_A4_B9") (pintype "power_in"))
      (node (ref "J4") (pin "A9_B4") (pinfunction "VBUS_A9_B4") (pintype "power_in"))
      (node (ref "U1") (pin "P$AD2") (pinfunction "VBUS_P$AD2") (pintype "power_in"))
    )
    (net (code "97") (name "VREG") (class "Default")
      (node (ref "C23") (pin "2") (pinfunction "2_2") (pintype "passive"))
      (node (ref "C24") (pin "2") (pinfunction "2_2") (pintype "passive"))
      (node (ref "C39") (pin "1") (pinfunction "1_1") (pintype "passive"))
      (node (ref "IC1") (pin "B2") (pinfunction "SYS_B2") (pintype "bidirectional"))
      (node (ref "IC9") (pin "A1") (pinfunction "EN_A1") (pintype "bidirectional"))
      (node (ref "IC9") (pin "A2") (pinfunction "VIN_1_A2") (pintype "bidirectional"))
      (node (ref "IC9") (pin "A3") (pinfunction "VIN_2_A3") (pintype "bidirectional"))
      (node (ref "TP_VREG") (pin "TP") (pinfunction "TP_TP") (pintype "input"))
    )
    (net (code "98") (name "unconnected-(ANT1-NC-Pad2)") (class "Default")
      (node (ref "ANT1") (pin "2") (pinfunction "NC_2") (pintype "no_connect"))
    )
    (net (code "99") (name "unconnected-(IC3-ASCL-Pad11)") (class "Default")
      (node (ref "IC3") (pin "11") (pinfunction "ASCL_11") (pintype "bidirectional"))
    )
    (net (code "100") (name "unconnected-(IC3-ASDA-Pad4)") (class "Default")
      (node (ref "IC3") (pin "4") (pinfunction "ASDA_4") (pintype "bidirectional"))
    )
    (net (code "101") (name "unconnected-(J1-Pad1)") (class "Default")
      (node (ref "J1") (pin "1") (pinfunction "1_1") (pintype "bidirectional"))
    )
    (net (code "102") (name "unconnected-(J1-Pad6)") (class "Default")
      (node (ref "J1") (pin "6") (pinfunction "6_6") (pintype "bidirectional"))
    )
    (net (code "103") (name "unconnected-(J1-Pad7)") (class "Default")
      (node (ref "J1") (pin "7") (pinfunction "7_7") (pintype "bidirectional"))
    )
    (net (code "104") (name "unconnected-(J4-SBU1-PadA8)") (class "Default")
      (node (ref "J4") (pin "A8") (pinfunction "SBU1_A8") (pintype "bidirectional"))
    )
    (net (code "105") (name "unconnected-(J4-SBU2-PadB8)") (class "Default")
      (node (ref "J4") (pin "B8") (pinfunction "SBU2_B8") (pintype "bidirectional"))
    )
    (net (code "106") (name "unconnected-(U1-DCCH-PadP$AB2)") (class "Default")
      (node (ref "U1") (pin "P$AB2") (pinfunction "DCCH_P$AB2") (pintype "bidirectional"))
    )
  )
)
